# relay_pcb2.net
KiCad netlist of a schematic drawn in EAGLE
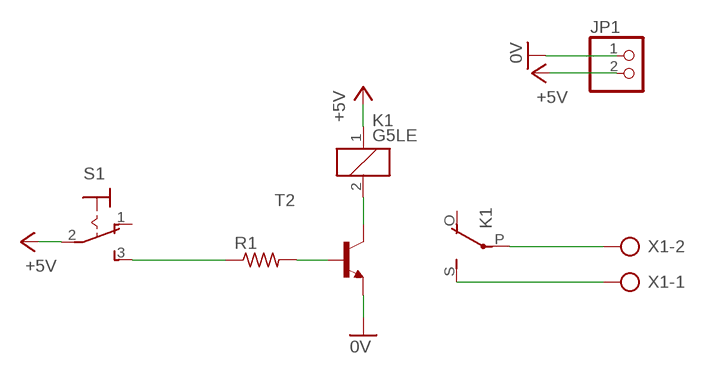
[diagram p0: schematic, sheet 1]

(export (version "E")
  (design (tool "Eeschema 10.0.6"))
  (components
    (comp (ref "JP1")
      (value "PINHD-1X2")
      (footprint "eagle-import:1X02")
      (libsource (lib "eagle-import") (part "PINHD-1X2"))
    )
    (comp (ref "K1")
      (value "G5LE")
      (footprint "eagle-import:G5LE")
      (libsource (lib "eagle-import") (part "G5LE"))
    )
    (comp (ref "R1")
      (value "R-US_0207/10")
      (footprint "eagle-import:0207_10")
      (libsource (lib "eagle-import") (part "R-US_0207/10"))
    )
    (comp (ref "S1")
      (value "M9040P")
      (footprint "eagle-import:M9040P")
      (libsource (lib "eagle-import") (part "M9040P"))
    )
    (comp (ref "T2")
      (value "BC618-NPN-TO92-CBE")
      (footprint "eagle-import:TO92-CBE")
      (libsource (lib "eagle-import") (part "-NPN-TO92-CBEBC618"))
    )
    (comp (ref "X1")
      (value "AK500/2")
      (footprint "eagle-import:AK500_2")
      (libsource (lib "eagle-import") (part "AK500/2"))
    )
  )
  (nets
    (net (code "1") (name "+5V") (class "Default")
      (node (ref "JP1") (pin "2") (pinfunction "2_2") (pintype "passive"))
      (node (ref "K1") (pin "1") (pinfunction "1_1") (pintype "passive"))
      (node (ref "S1") (pin "2") (pinfunction "P_2") (pintype "passive"))
    )
    (net (code "2") (name "0V") (class "Default")
      (node (ref "JP1") (pin "1") (pinfunction "1_1") (pintype "passive"))
      (node (ref "T2") (pin "E") (pinfunction "E_E") (pintype "passive"))
    )
    (net (code "3") (name "Net-(K1-Pad2)") (class "Default")
      (node (ref "K1") (pin "2") (pinfunction "2_2") (pintype "passive"))
      (node (ref "T2") (pin "C") (pinfunction "C_C") (pintype "passive"))
    )
    (net (code "4") (name "Net-(R1-Pad2)") (class "Default")
      (node (ref "R1") (pin "2") (pinfunction "2_2") (pintype "passive"))
      (node (ref "T2") (pin "B") (pinfunction "B_B") (pintype "passive"))
    )
    (net (code "5") (name "Net-(S1-S)") (class "Default")
      (node (ref "R1") (pin "1") (pinfunction "1_1") (pintype "passive"))
      (node (ref "S1") (pin "3") (pinfunction "S_3") (pintype "passive"))
    )
    (net (code "6") (name "Net-(X1A-KL)") (class "Default")
      (node (ref "K1") (pin "S") (pinfunction "S_S") (pintype "passive"))
      (node (ref "X1") (pin "1") (pinfunction "KL_1") (pintype "passive"))
    )
    (net (code "7") (name "Net-(X1B-KL)") (class "Default")
      (node (ref "K1") (pin "P") (pinfunction "P_P") (pintype "passive"))
      (node (ref "X1") (pin "2") (pinfunction "KL_2") (pintype "passive"))
    )
    (net (code "8") (name "unconnected-(K1-PadO)") (class "Default")
      (node (ref "K1") (pin "O") (pinfunction "O_O") (pintype "passive"))
    )
    (net (code "9") (name "unconnected-(S1-O-Pad1)") (class "Default")
      (node (ref "S1") (pin "1") (pinfunction "O_1") (pintype "passive"))
    )
  )
)
